# dsbrut2.net
KiCad netlist of a schematic drawn in EAGLE
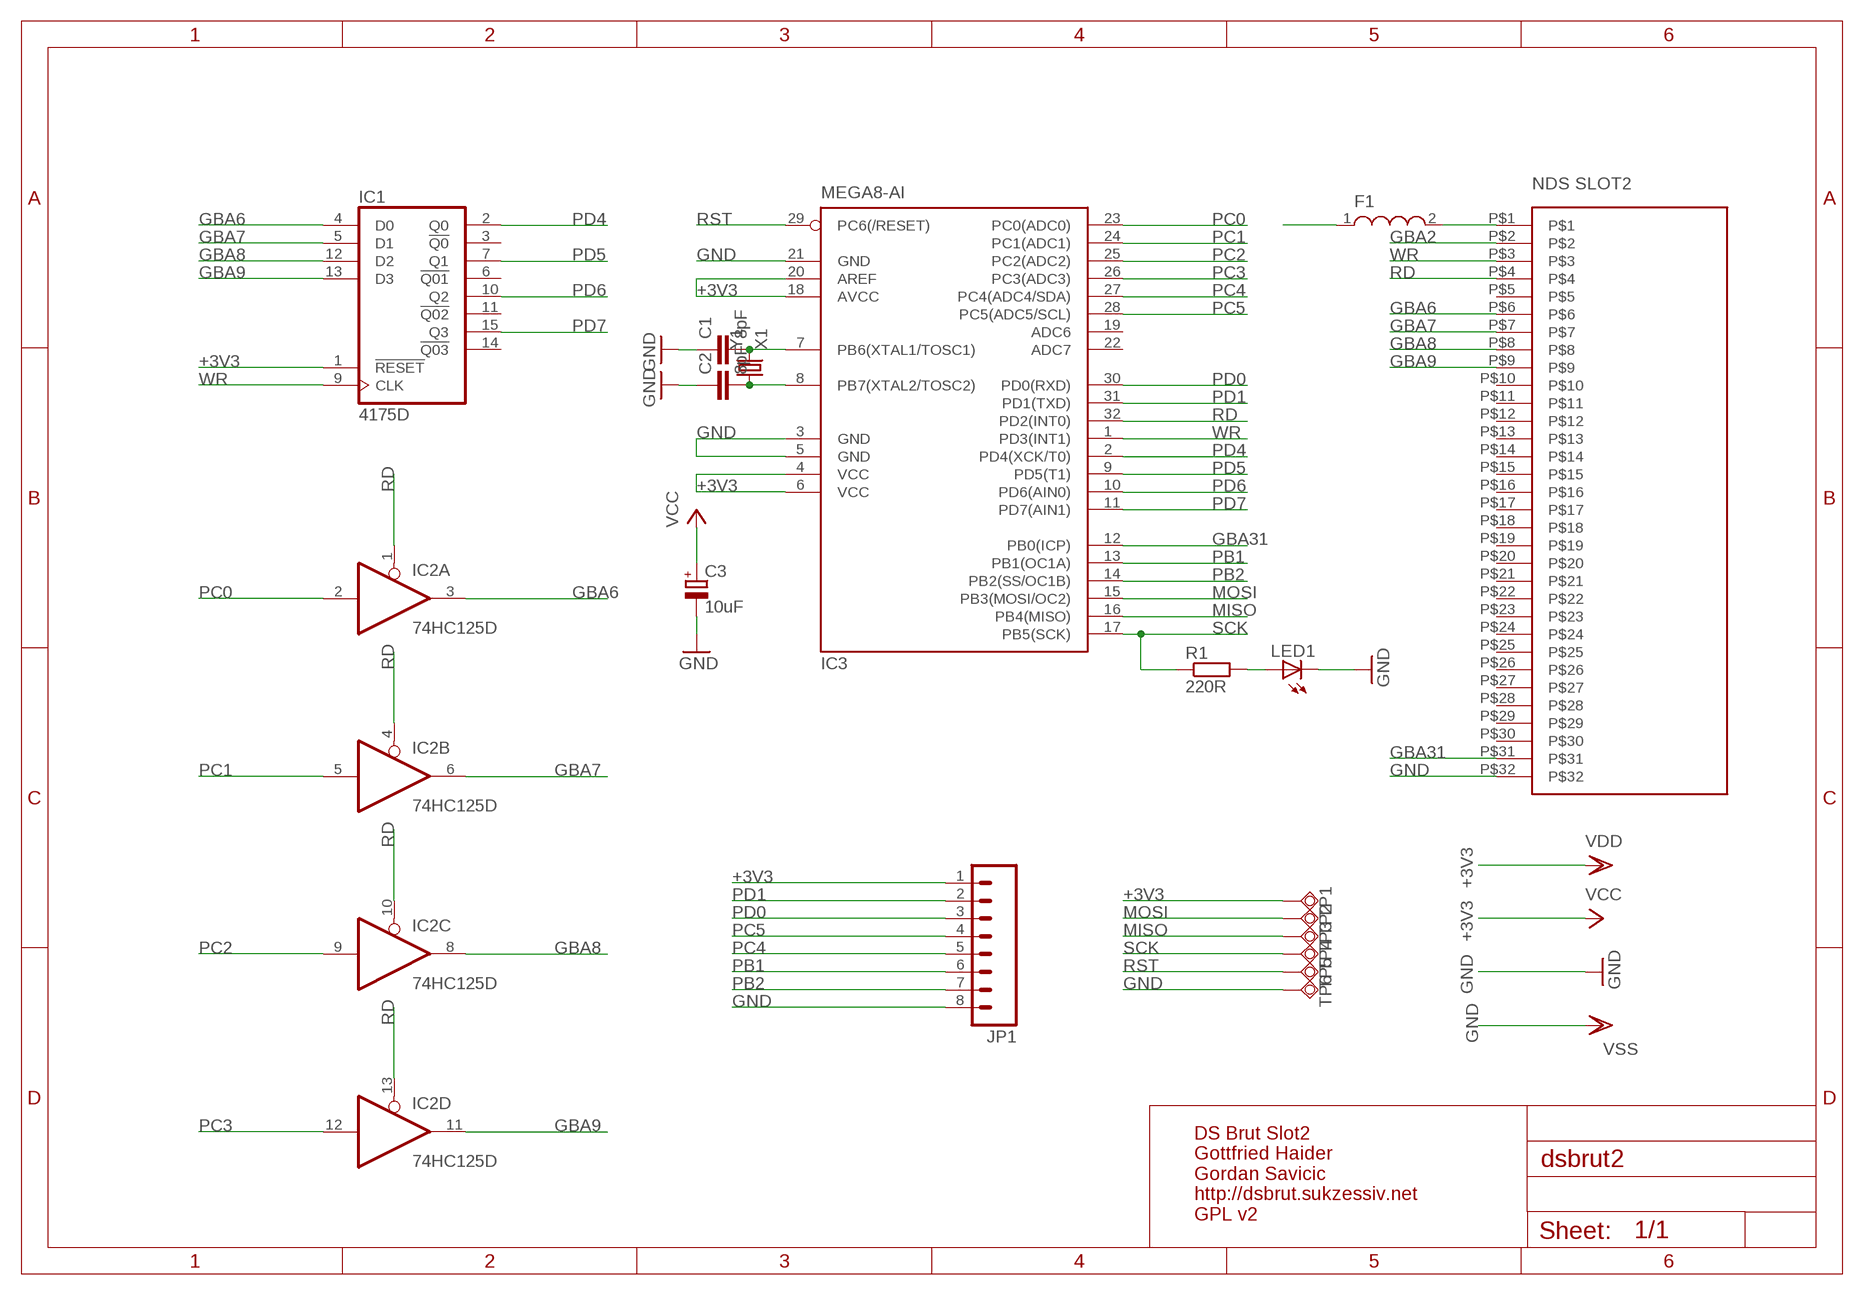
[diagram p0: schematic, sheet 1]

(export (version "E")
  (design (tool "Eeschema 10.0.6"))
  (components
    (comp (ref "C1")
      (value "8pF")
      (footprint "eagle-import:C0603K")
      (libsource (lib "eagle-import") (part "C-EUC0603K"))
    )
    (comp (ref "C2")
      (value "8pF")
      (footprint "eagle-import:C0603K")
      (libsource (lib "eagle-import") (part "C-EUC0603K"))
    )
    (comp (ref "C3")
      (value "10uF")
      (footprint "eagle-import:SMC_A")
      (libsource (lib "eagle-import") (part "CPOL-EUSMCA"))
    )
    (comp (ref "F1")
      (value "F1")
      (footprint "eagle-import:L1812")
      (libsource (lib "eagle-import") (part "INDUCTOR-L1812"))
    )
    (comp (ref "IC1")
      (value "4175D")
      (footprint "eagle-import:SO16")
      (libsource (lib "eagle-import") (part "4175D"))
    )
    (comp (ref "IC2")
      (value "74HC125D")
      (footprint "eagle-import:SO14")
      (libsource (lib "eagle-import") (part "74125DHC"))
    )
    (comp (ref "IC3")
      (value "MEGA8-AI")
      (footprint "eagle-import:TQFP32-08")
      (fields (field (name "MPN") "ATMEGA8-16AU"))
      (libsource (lib "eagle-import") (part "MEGA8-AI"))
    )
    (comp (ref "JP1")
      (value "M08LONGPADS")
      (footprint "eagle-import:1X08_LONGPADS")
      (libsource (lib "eagle-import") (part "M08LONGPADS"))
    )
    (comp (ref "LED1")
      (value "LED0603")
      (footprint "eagle-import:LED-0603")
      (libsource (lib "eagle-import") (part "LED0603"))
    )
    (comp (ref "R1")
      (value "220R")
      (footprint "eagle-import:M0805")
      (libsource (lib "eagle-import") (part "R-EU_M0805"))
    )
    (comp (ref "TP1")
      (value "TPSQTP16R")
      (footprint "eagle-import:TP16R")
      (libsource (lib "eagle-import") (part "TPSQTP16R"))
    )
    (comp (ref "TP2")
      (value "TPSQTP16R")
      (footprint "eagle-import:TP16R")
      (libsource (lib "eagle-import") (part "TPSQTP16R"))
    )
    (comp (ref "TP3")
      (value "TPSQTP16SQ")
      (footprint "eagle-import:TP16SQ")
      (libsource (lib "eagle-import") (part "TPSQTP16SQ"))
    )
    (comp (ref "TP4")
      (value "TPSQTP16R")
      (footprint "eagle-import:TP16R")
      (libsource (lib "eagle-import") (part "TPSQTP16R"))
    )
    (comp (ref "TP5")
      (value "TPSQTP16R")
      (footprint "eagle-import:TP16R")
      (libsource (lib "eagle-import") (part "TPSQTP16R"))
    )
    (comp (ref "TP6")
      (value "TPSQTP16R")
      (footprint "eagle-import:TP16R")
      (libsource (lib "eagle-import") (part "TPSQTP16R"))
    )
    (comp (ref "U$1")
      (value "DS_CARTRIDGE_SLOT2")
      (footprint "eagle-import:DS-CARTRIDGE-SLOT2")
      (libsource (lib "eagle-import") (part "DS_CARTRIDGE_SLOT2"))
    )
    (comp (ref "Y1")
      (value "X1")
      (footprint "eagle-import:CRYSTAL-SMD-5X3")
      (libsource (lib "eagle-import") (part "CRYSTAL5X3"))
    )
  )
  (nets
    (net (code "1") (name "/GBA2") (class "Default")
      (node (ref "U$1") (pin "P$2") (pinfunction "P$2_P$2") (pintype "bidirectional"))
    )
    (net (code "2") (name "/GBA6") (class "Default")
      (node (ref "IC1") (pin "4") (pinfunction "D0_4") (pintype "input"))
      (node (ref "IC2") (pin "3") (pinfunction "O_3") (pintype "tri_state"))
      (node (ref "U$1") (pin "P$6") (pinfunction "P$6_P$6") (pintype "bidirectional"))
    )
    (net (code "3") (name "/GBA7") (class "Default")
      (node (ref "IC1") (pin "5") (pinfunction "D1_5") (pintype "input"))
      (node (ref "IC2") (pin "6") (pinfunction "O_6") (pintype "tri_state"))
      (node (ref "U$1") (pin "P$7") (pinfunction "P$7_P$7") (pintype "bidirectional"))
    )
    (net (code "4") (name "/GBA8") (class "Default")
      (node (ref "IC1") (pin "12") (pinfunction "D2_12") (pintype "input"))
      (node (ref "IC2") (pin "8") (pinfunction "O_8") (pintype "tri_state"))
      (node (ref "U$1") (pin "P$8") (pinfunction "P$8_P$8") (pintype "bidirectional"))
    )
    (net (code "5") (name "/GBA9") (class "Default")
      (node (ref "IC1") (pin "13") (pinfunction "D3_13") (pintype "input"))
      (node (ref "IC2") (pin "11") (pinfunction "O_11") (pintype "tri_state"))
      (node (ref "U$1") (pin "P$9") (pinfunction "P$9_P$9") (pintype "bidirectional"))
    )
    (net (code "6") (name "/GBA31") (class "Default")
      (node (ref "IC3") (pin "12") (pinfunction "PB0(ICP)_12") (pintype "bidirectional"))
      (node (ref "U$1") (pin "P$31") (pinfunction "P$31_P$31") (pintype "bidirectional"))
    )
    (net (code "7") (name "/MISO") (class "Default")
      (node (ref "IC3") (pin "16") (pinfunction "PB4(MISO)_16") (pintype "bidirectional"))
      (node (ref "TP3") (pin "TP") (pinfunction "TP_TP") (pintype "input"))
    )
    (net (code "8") (name "/MOSI") (class "Default")
      (node (ref "IC3") (pin "15") (pinfunction "PB3(MOSI/OC2)_15") (pintype "bidirectional"))
      (node (ref "TP2") (pin "TP") (pinfunction "TP_TP") (pintype "input"))
    )
    (net (code "9") (name "/PB1") (class "Default")
      (node (ref "IC3") (pin "13") (pinfunction "PB1(OC1A)_13") (pintype "bidirectional"))
      (node (ref "JP1") (pin "6") (pinfunction "6_6") (pintype "passive"))
    )
    (net (code "10") (name "/PB2") (class "Default")
      (node (ref "IC3") (pin "14") (pinfunction "PB2(SS/OC1B)_14") (pintype "bidirectional"))
      (node (ref "JP1") (pin "7") (pinfunction "7_7") (pintype "passive"))
    )
    (net (code "11") (name "/PC0") (class "Default")
      (node (ref "IC2") (pin "2") (pinfunction "I_2") (pintype "input"))
      (node (ref "IC3") (pin "23") (pinfunction "PC0(ADC0)_23") (pintype "bidirectional"))
    )
    (net (code "12") (name "/PC1") (class "Default")
      (node (ref "IC2") (pin "5") (pinfunction "I_5") (pintype "input"))
      (node (ref "IC3") (pin "24") (pinfunction "PC1(ADC1)_24") (pintype "bidirectional"))
    )
    (net (code "13") (name "/PC2") (class "Default")
      (node (ref "IC2") (pin "9") (pinfunction "I_9") (pintype "input"))
      (node (ref "IC3") (pin "25") (pinfunction "PC2(ADC2)_25") (pintype "bidirectional"))
    )
    (net (code "14") (name "/PC3") (class "Default")
      (node (ref "IC2") (pin "12") (pinfunction "I_12") (pintype "input"))
      (node (ref "IC3") (pin "26") (pinfunction "PC3(ADC3)_26") (pintype "bidirectional"))
    )
    (net (code "15") (name "/PC4") (class "Default")
      (node (ref "IC3") (pin "27") (pinfunction "PC4(ADC4/SDA)_27") (pintype "bidirectional"))
      (node (ref "JP1") (pin "5") (pinfunction "5_5") (pintype "passive"))
    )
    (net (code "16") (name "/PC5") (class "Default")
      (node (ref "IC3") (pin "28") (pinfunction "PC5(ADC5/SCL)_28") (pintype "bidirectional"))
      (node (ref "JP1") (pin "4") (pinfunction "4_4") (pintype "passive"))
    )
    (net (code "17") (name "/PD0") (class "Default")
      (node (ref "IC3") (pin "30") (pinfunction "PD0(RXD)_30") (pintype "bidirectional"))
      (node (ref "JP1") (pin "3") (pinfunction "3_3") (pintype "passive"))
    )
    (net (code "18") (name "/PD1") (class "Default")
      (node (ref "IC3") (pin "31") (pinfunction "PD1(TXD)_31") (pintype "bidirectional"))
      (node (ref "JP1") (pin "2") (pinfunction "2_2") (pintype "passive"))
    )
    (net (code "19") (name "/PD4") (class "Default")
      (node (ref "IC1") (pin "2") (pinfunction "Q0_2") (pintype "output"))
      (node (ref "IC3") (pin "2") (pinfunction "PD4(XCK/T0)_2") (pintype "bidirectional"))
    )
    (net (code "20") (name "/PD5") (class "Default")
      (node (ref "IC1") (pin "7") (pinfunction "Q1_7") (pintype "output"))
      (node (ref "IC3") (pin "9") (pinfunction "PD5(T1)_9") (pintype "bidirectional"))
    )
    (net (code "21") (name "/PD6") (class "Default")
      (node (ref "IC1") (pin "10") (pinfunction "Q2_10") (pintype "output"))
      (node (ref "IC3") (pin "10") (pinfunction "PD6(AIN0)_10") (pintype "bidirectional"))
    )
    (net (code "22") (name "/PD7") (class "Default")
      (node (ref "IC1") (pin "15") (pinfunction "Q3_15") (pintype "output"))
      (node (ref "IC3") (pin "11") (pinfunction "PD7(AIN1)_11") (pintype "bidirectional"))
    )
    (net (code "23") (name "/RD") (class "Default")
      (node (ref "IC2") (pin "1") (pinfunction "OE_1") (pintype "input"))
      (node (ref "IC2") (pin "10") (pinfunction "OE_10") (pintype "input"))
      (node (ref "IC2") (pin "13") (pinfunction "OE_13") (pintype "input"))
      (node (ref "IC2") (pin "4") (pinfunction "OE_4") (pintype "input"))
      (node (ref "IC3") (pin "32") (pinfunction "PD2(INT0)_32") (pintype "bidirectional"))
      (node (ref "U$1") (pin "P$4") (pinfunction "P$4_P$4") (pintype "bidirectional"))
    )
    (net (code "24") (name "/RST") (class "Default")
      (node (ref "IC3") (pin "29") (pinfunction "PC6(/RESET)_29") (pintype "bidirectional"))
      (node (ref "TP5") (pin "TP") (pinfunction "TP_TP") (pintype "input"))
    )
    (net (code "25") (name "/SCK") (class "Default")
      (node (ref "IC3") (pin "17") (pinfunction "PB5(SCK)_17") (pintype "bidirectional"))
      (node (ref "R1") (pin "1") (pinfunction "1_1") (pintype "passive"))
      (node (ref "TP4") (pin "TP") (pinfunction "TP_TP") (pintype "input"))
    )
    (net (code "26") (name "/WR") (class "Default")
      (node (ref "IC1") (pin "9") (pinfunction "CLK_9") (pintype "input"))
      (node (ref "IC3") (pin "1") (pinfunction "PD3(INT1)_1") (pintype "bidirectional"))
      (node (ref "U$1") (pin "P$3") (pinfunction "P$3_P$3") (pintype "bidirectional"))
    )
    (net (code "27") (name "GND") (class "Default")
      (node (ref "C1") (pin "1") (pinfunction "1_1") (pintype "passive"))
      (node (ref "C2") (pin "1") (pinfunction "1_1") (pintype "passive"))
      (node (ref "C3") (pin "-") (pinfunction "-_-") (pintype "passive"))
      (node (ref "IC3") (pin "21") (pinfunction "GND_21") (pintype "power_in"))
      (node (ref "IC3") (pin "3") (pinfunction "GND_3") (pintype "power_in"))
      (node (ref "IC3") (pin "5") (pinfunction "GND_5") (pintype "power_in"))
      (node (ref "JP1") (pin "8") (pinfunction "8_8") (pintype "passive"))
      (node (ref "LED1") (pin "C") (pinfunction "C_C") (pintype "passive"))
      (node (ref "TP6") (pin "TP") (pinfunction "TP_TP") (pintype "input"))
      (node (ref "U$1") (pin "P$32") (pinfunction "P$32_P$32") (pintype "bidirectional"))
    )
    (net (code "28") (name "Net-(F1-Pad2)") (class "Default")
      (node (ref "F1") (pin "2") (pinfunction "2_2") (pintype "passive"))
      (node (ref "U$1") (pin "P$1") (pinfunction "P$1_P$1") (pintype "bidirectional"))
    )
    (net (code "29") (name "Net-(IC3-PB6(XTAL1{slash}TOSC1))") (class "Default")
      (node (ref "C1") (pin "2") (pinfunction "2_2") (pintype "passive"))
      (node (ref "IC3") (pin "7") (pinfunction "PB6(XTAL1/TOSC1)_7") (pintype "bidirectional"))
      (node (ref "Y1") (pin "3") (pinfunction "2_3") (pintype "passive"))
    )
    (net (code "30") (name "Net-(IC3-PB7(XTAL2{slash}TOSC2))") (class "Default")
      (node (ref "C2") (pin "2") (pinfunction "2_2") (pintype "passive"))
      (node (ref "IC3") (pin "8") (pinfunction "PB7(XTAL2/TOSC2)_8") (pintype "bidirectional"))
      (node (ref "Y1") (pin "1") (pinfunction "1_1") (pintype "passive"))
    )
    (net (code "31") (name "Net-(LED1-PadA)") (class "Default")
      (node (ref "LED1") (pin "A") (pinfunction "A_A") (pintype "passive"))
      (node (ref "R1") (pin "2") (pinfunction "2_2") (pintype "passive"))
    )
    (net (code "32") (name "VCC") (class "Default")
      (node (ref "C3") (pin "+") (pinfunction "+_+") (pintype "passive"))
      (node (ref "F1") (pin "1") (pinfunction "1_1") (pintype "passive"))
      (node (ref "IC1") (pin "1") (pinfunction "~{RESET}_1") (pintype "input"))
      (node (ref "IC3") (pin "18") (pinfunction "AVCC_18") (pintype "power_in"))
      (node (ref "IC3") (pin "20") (pinfunction "AREF_20") (pintype "passive"))
      (node (ref "IC3") (pin "4") (pinfunction "VCC_4") (pintype "power_in"))
      (node (ref "IC3") (pin "6") (pinfunction "VCC_6") (pintype "power_in"))
      (node (ref "JP1") (pin "1") (pinfunction "1_1") (pintype "passive"))
      (node (ref "TP1") (pin "TP") (pinfunction "TP_TP") (pintype "input"))
    )
    (net (code "33") (name "unconnected-(IC1A-~{Q0}-Pad3)") (class "Default")
      (node (ref "IC1") (pin "3") (pinfunction "~{Q0}_3") (pintype "output"))
    )
    (net (code "34") (name "unconnected-(IC1A-~{Q01}-Pad6)") (class "Default")
      (node (ref "IC1") (pin "6") (pinfunction "~{Q01}_6") (pintype "output"))
    )
    (net (code "35") (name "unconnected-(IC1A-~{Q02}-Pad11)") (class "Default")
      (node (ref "IC1") (pin "11") (pinfunction "~{Q02}_11") (pintype "output"))
    )
    (net (code "36") (name "unconnected-(IC1A-~{Q03}-Pad14)") (class "Default")
      (node (ref "IC1") (pin "14") (pinfunction "~{Q03}_14") (pintype "output"))
    )
    (net (code "37") (name "unconnected-(IC3-ADC6-Pad19)") (class "Default")
      (node (ref "IC3") (pin "19") (pinfunction "ADC6_19") (pintype "bidirectional"))
    )
    (net (code "38") (name "unconnected-(IC3-ADC7-Pad22)") (class "Default")
      (node (ref "IC3") (pin "22") (pinfunction "ADC7_22") (pintype "bidirectional"))
    )
    (net (code "39") (name "unconnected-(U$1-PadP$5)") (class "Default")
      (node (ref "U$1") (pin "P$5") (pinfunction "P$5_P$5") (pintype "bidirectional"))
    )
    (net (code "40") (name "unconnected-(U$1-PadP$10)") (class "Default")
      (node (ref "U$1") (pin "P$10") (pinfunction "P$10_P$10") (pintype "bidirectional"))
    )
    (net (code "41") (name "unconnected-(U$1-PadP$11)") (class "Default")
      (node (ref "U$1") (pin "P$11") (pinfunction "P$11_P$11") (pintype "bidirectional"))
    )
    (net (code "42") (name "unconnected-(U$1-PadP$12)") (class "Default")
      (node (ref "U$1") (pin "P$12") (pinfunction "P$12_P$12") (pintype "bidirectional"))
    )
    (net (code "43") (name "unconnected-(U$1-PadP$13)") (class "Default")
      (node (ref "U$1") (pin "P$13") (pinfunction "P$13_P$13") (pintype "bidirectional"))
    )
    (net (code "44") (name "unconnected-(U$1-PadP$14)") (class "Default")
      (node (ref "U$1") (pin "P$14") (pinfunction "P$14_P$14") (pintype "bidirectional"))
    )
    (net (code "45") (name "unconnected-(U$1-PadP$15)") (class "Default")
      (node (ref "U$1") (pin "P$15") (pinfunction "P$15_P$15") (pintype "bidirectional"))
    )
    (net (code "46") (name "unconnected-(U$1-PadP$16)") (class "Default")
      (node (ref "U$1") (pin "P$16") (pinfunction "P$16_P$16") (pintype "bidirectional"))
    )
    (net (code "47") (name "unconnected-(U$1-PadP$17)") (class "Default")
      (node (ref "U$1") (pin "P$17") (pinfunction "P$17_P$17") (pintype "bidirectional"))
    )
    (net (code "48") (name "unconnected-(U$1-PadP$18)") (class "Default")
      (node (ref "U$1") (pin "P$18") (pinfunction "P$18_P$18") (pintype "bidirectional"))
    )
    (net (code "49") (name "unconnected-(U$1-PadP$19)") (class "Default")
      (node (ref "U$1") (pin "P$19") (pinfunction "P$19_P$19") (pintype "bidirectional"))
    )
    (net (code "50") (name "unconnected-(U$1-PadP$20)") (class "Default")
      (node (ref "U$1") (pin "P$20") (pinfunction "P$20_P$20") (pintype "bidirectional"))
    )
    (net (code "51") (name "unconnected-(U$1-PadP$21)") (class "Default")
      (node (ref "U$1") (pin "P$21") (pinfunction "P$21_P$21") (pintype "bidirectional"))
    )
    (net (code "52") (name "unconnected-(U$1-PadP$22)") (class "Default")
      (node (ref "U$1") (pin "P$22") (pinfunction "P$22_P$22") (pintype "bidirectional"))
    )
    (net (code "53") (name "unconnected-(U$1-PadP$23)") (class "Default")
      (node (ref "U$1") (pin "P$23") (pinfunction "P$23_P$23") (pintype "bidirectional"))
    )
    (net (code "54") (name "unconnected-(U$1-PadP$24)") (class "Default")
      (node (ref "U$1") (pin "P$24") (pinfunction "P$24_P$24") (pintype "bidirectional"))
    )
    (net (code "55") (name "unconnected-(U$1-PadP$25)") (class "Default")
      (node (ref "U$1") (pin "P$25") (pinfunction "P$25_P$25") (pintype "bidirectional"))
    )
    (net (code "56") (name "unconnected-(U$1-PadP$26)") (class "Default")
      (node (ref "U$1") (pin "P$26") (pinfunction "P$26_P$26") (pintype "bidirectional"))
    )
    (net (code "57") (name "unconnected-(U$1-PadP$27)") (class "Default")
      (node (ref "U$1") (pin "P$27") (pinfunction "P$27_P$27") (pintype "bidirectional"))
    )
    (net (code "58") (name "unconnected-(U$1-PadP$28)") (class "Default")
      (node (ref "U$1") (pin "P$28") (pinfunction "P$28_P$28") (pintype "bidirectional"))
    )
    (net (code "59") (name "unconnected-(U$1-PadP$29)") (class "Default")
      (node (ref "U$1") (pin "P$29") (pinfunction "P$29_P$29") (pintype "bidirectional"))
    )
    (net (code "60") (name "unconnected-(U$1-PadP$30)") (class "Default")
      (node (ref "U$1") (pin "P$30") (pinfunction "P$30_P$30") (pintype "bidirectional"))
    )
  )
)
